# motion_tracker.net
KiCad netlist of a schematic drawn in Altium Designer
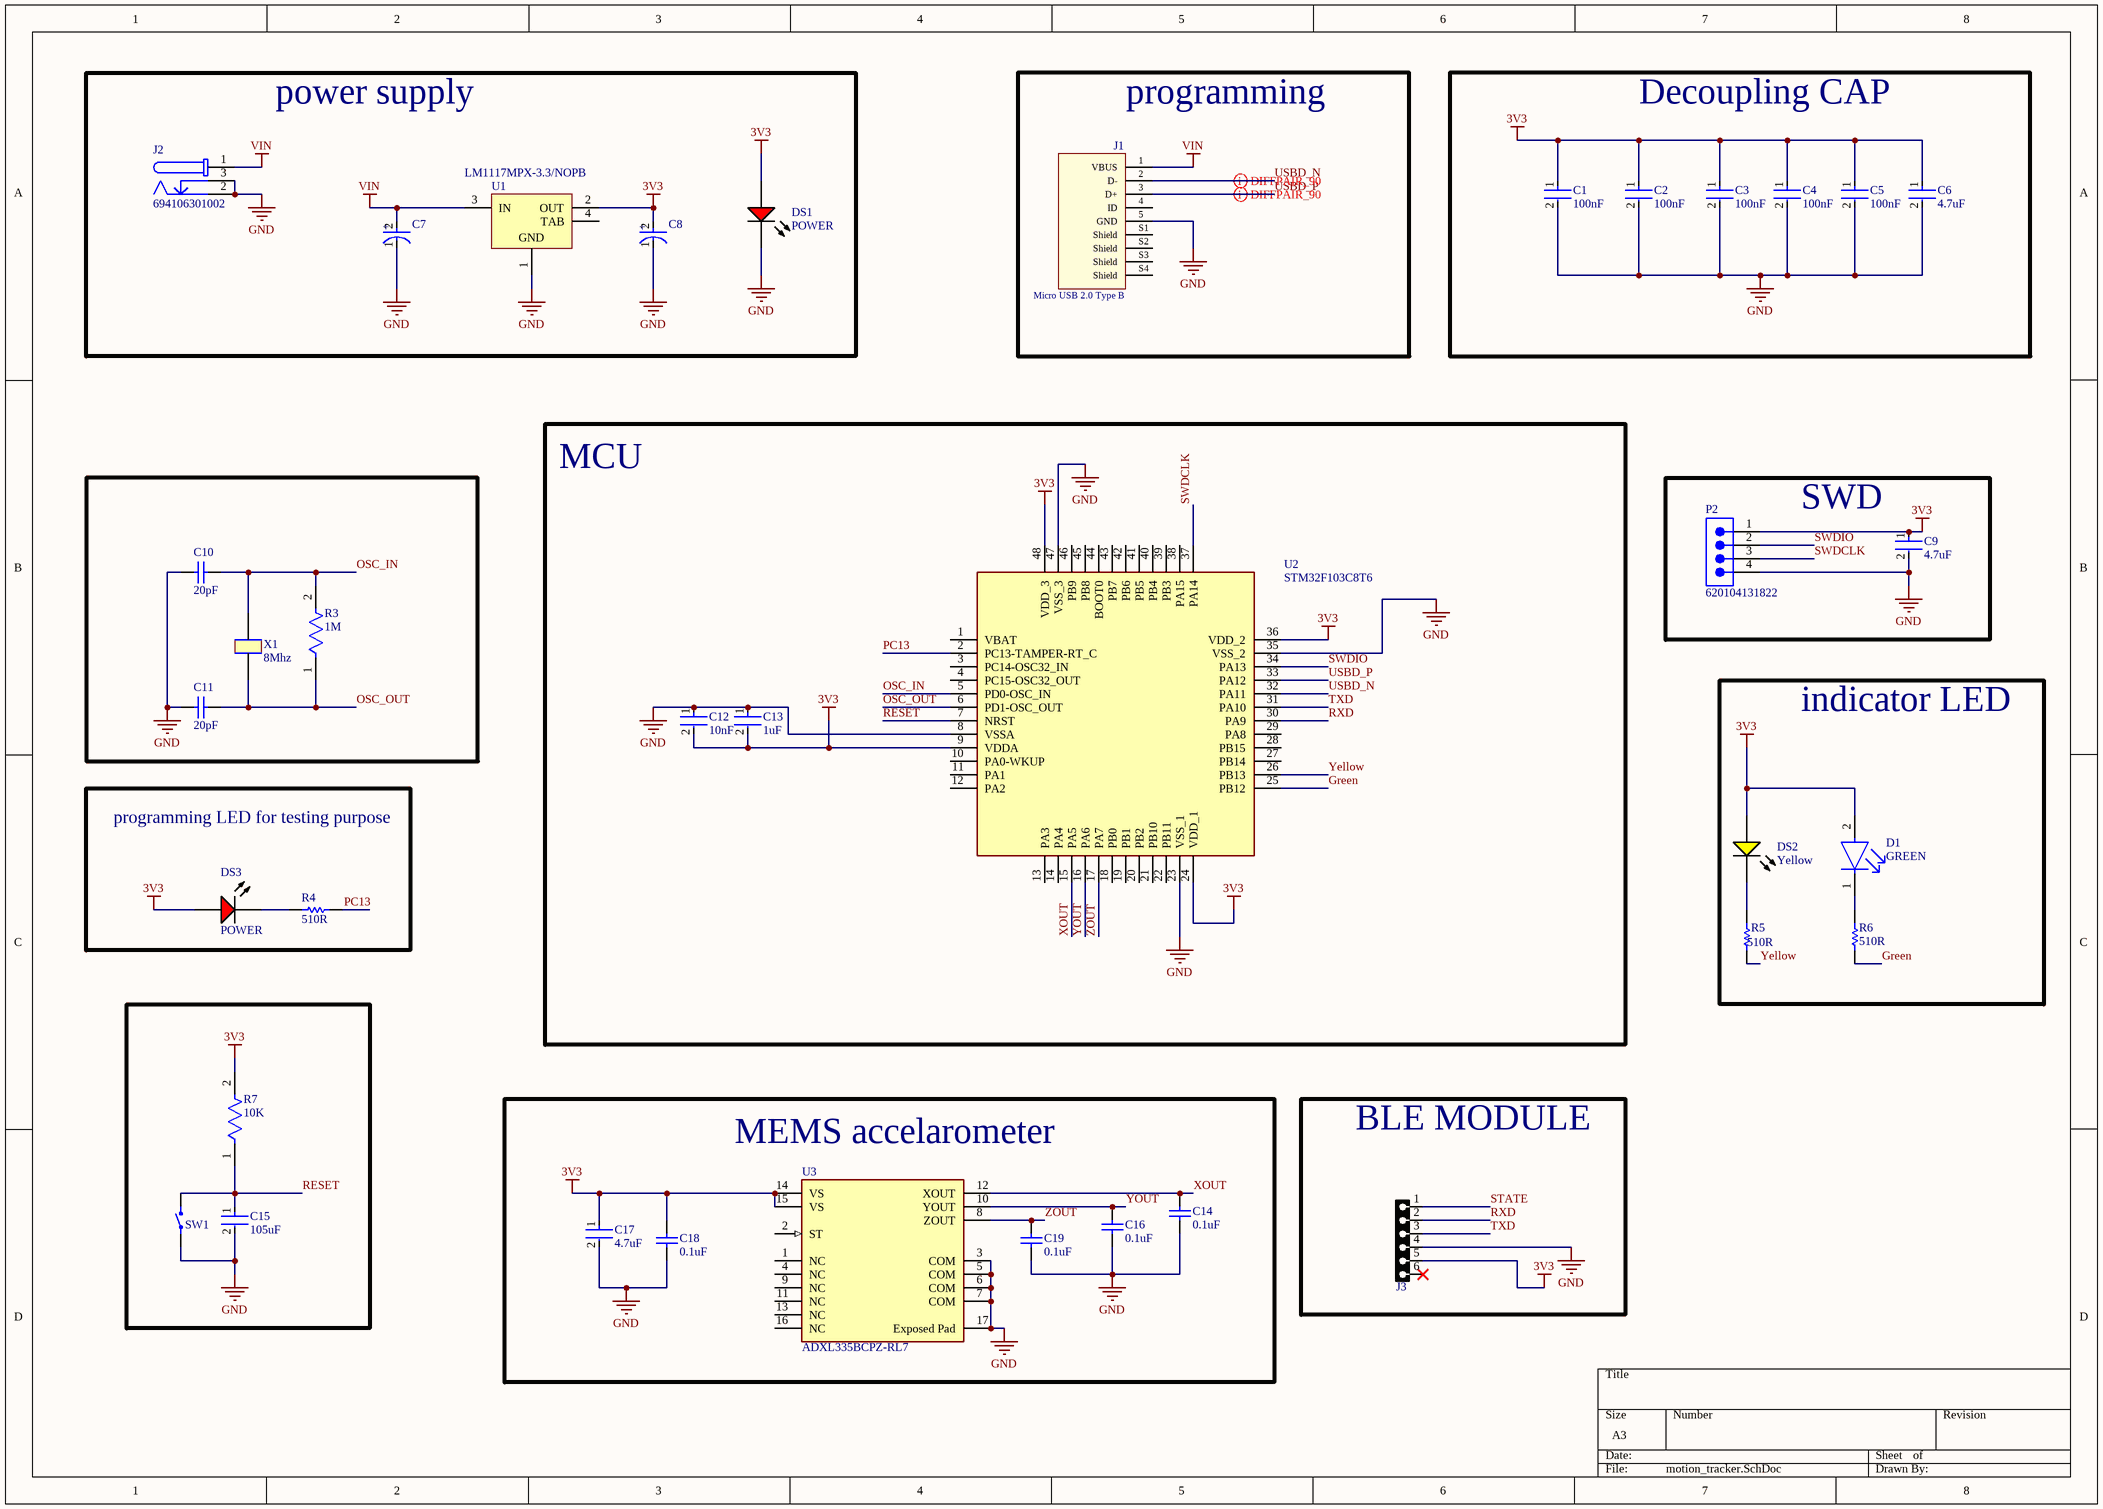
[diagram p0: motion_tracker.SchDoc]

(export (version "E")
  (design (tool "Eeschema 10.0.6"))
  (components
    (comp (ref "C1")
      (value "100nF")
      (footprint "FP-0603-L_1_6_0_15-W_0_81-IPC_C")
      (description "Automotive Ceramic Capacitor, 0603, 100nF, 10%, X7R, 15%, 50V")
      (fields (field (name "VOLTAGE") "50V") (field (name "TOLERANCE") "10%"))
      (libsource (lib "Altium Content Vault") (part "02cd4be3c70576c341d710602a673aa"))
    )
    (comp (ref "C2")
      (value "100nF")
      (footprint "FP-0603-L_1_6_0_15-W_0_81-IPC_C")
      (description "Automotive Ceramic Capacitor, 0603, 100nF, 10%, X7R, 15%, 50V")
      (fields (field (name "VOLTAGE") "50V") (field (name "TOLERANCE") "10%"))
      (libsource (lib "Altium Content Vault") (part "02cd4be3c70576c341d710602a673aa"))
    )
    (comp (ref "C3")
      (value "100nF")
      (footprint "FP-0603-L_1_6_0_15-W_0_81-IPC_C")
      (description "Automotive Ceramic Capacitor, 0603, 100nF, 10%, X7R, 15%, 50V")
      (fields (field (name "VOLTAGE") "50V") (field (name "TOLERANCE") "10%"))
      (libsource (lib "Altium Content Vault") (part "02cd4be3c70576c341d710602a673aa"))
    )
    (comp (ref "C4")
      (value "100nF")
      (footprint "FP-0603-L_1_6_0_15-W_0_81-IPC_C")
      (description "Automotive Ceramic Capacitor, 0603, 100nF, 10%, X7R, 15%, 50V")
      (fields (field (name "VOLTAGE") "50V") (field (name "TOLERANCE") "10%"))
      (libsource (lib "Altium Content Vault") (part "02cd4be3c70576c341d710602a673aa"))
    )
    (comp (ref "C5")
      (value "100nF")
      (footprint "FP-0603-L_1_6_0_15-W_0_81-IPC_C")
      (description "Automotive Ceramic Capacitor, 0603, 100nF, 10%, X7R, 15%, 50V")
      (fields (field (name "VOLTAGE") "50V") (field (name "TOLERANCE") "10%"))
      (libsource (lib "Altium Content Vault") (part "02cd4be3c70576c341d710602a673aa"))
    )
    (comp (ref "C6")
      (value "4.7uF")
      (footprint "FP-0603-L_1_6_0_15-W_0_81-IPC_A")
      (description "General Purpose Ceramic Capacitor, 0603, 4.7uF, 20%, X5R, 15%, 6.3V")
      (fields (field (name "TOLERANCE") "20%") (field (name "VOLTAGE") "6.3V"))
      (libsource (lib "Altium Content Vault") (part "02cd4be3c70576c341d710602a673aa"))
    )
    (comp (ref "C7")
      (value "EEEFP1C100AR")
      (footprint "FP-FPB-MFG")
      (fields (field (name "TOLERANCE") "20%") (field (name "VOLTAGE") "16V"))
      (libsource (lib "Altium Content Vault") (part "203bc49f2ac43e59fd269a8c329ed05"))
    )
    (comp (ref "C8")
      (value "EEEFP1C100AR")
      (footprint "FP-FPB-MFG")
      (fields (field (name "TOLERANCE") "20%") (field (name "VOLTAGE") "16V"))
      (libsource (lib "Altium Content Vault") (part "203bc49f2ac43e59fd269a8c329ed05"))
    )
    (comp (ref "C9")
      (value "4.7uF")
      (footprint "FP-0603-L_1_6_0_15-W_0_81-IPC_A")
      (description "General Purpose Ceramic Capacitor, 0603, 4.7uF, 20%, X5R, 15%, 6.3V")
      (fields (field (name "TOLERANCE") "20%") (field (name "VOLTAGE") "6.3V"))
      (libsource (lib "Altium Content Vault") (part "02cd4be3c70576c341d710602a673aa"))
    )
    (comp (ref "C10")
      (value "20pF")
      (footprint "CAPC1608X90X35NL15T15")
      (fields
        (field (name "PART NUMBER") "06035A200JAT2A")
        (field (name "MANUFACTURER") "AVX Interconnect / Elco")
      )
      (libsource (lib "Altium Content Vault") (part "CAP"))
    )
    (comp (ref "C11")
      (value "20pF")
      (footprint "CAPC1608X90X35NL15T15")
      (fields
        (field (name "PART NUMBER") "06035A200JAT2A")
        (field (name "MANUFACTURER") "AVX Interconnect / Elco")
      )
      (libsource (lib "Altium Content Vault") (part "CAP"))
    )
    (comp (ref "C12")
      (value "10nF")
      (footprint "FP-0603-L_1_6_0_15-W_0_81-IPC_C")
      (description "Automotive Ceramic Capacitor, 0603, 100nF, 10%, X7R, 15%, 50V")
      (fields (field (name "VOLTAGE") "50V") (field (name "TOLERANCE") "10%"))
      (libsource (lib "Altium Content Vault") (part "02cd4be3c70576c341d710602a673aa"))
    )
    (comp (ref "C13")
      (value "1uF")
      (footprint "FP-0603-L_1_6_0_15-W_0_81-IPC_C")
      (description "Automotive Ceramic Capacitor, 0603, 100nF, 10%, X7R, 15%, 50V")
      (fields (field (name "VOLTAGE") "50V") (field (name "TOLERANCE") "10%"))
      (libsource (lib "Altium Content Vault") (part "02cd4be3c70576c341d710602a673aa"))
    )
    (comp (ref "C14")
      (value "0.1uF")
      (footprint "CAPC1608X90X35LL15T15")
      (fields
        (field (name "MANUFACTURER") "AVX Interconnect / Elco")
        (field (name "PART NUMBER") "LD035C104KAB2A")
      )
      (libsource (lib "Altium Content Vault") (part "CAP"))
    )
    (comp (ref "C15")
      (value "105uF")
      (footprint "FP-0603-L_1_6_0_15-W_0_81-IPC_C")
      (description "Automotive Ceramic Capacitor, 0603, 100nF, 10%, X7R, 15%, 50V")
      (fields (field (name "VOLTAGE") "50V") (field (name "TOLERANCE") "10%"))
      (libsource (lib "Altium Content Vault") (part "02cd4be3c70576c341d710602a673aa"))
    )
    (comp (ref "C16")
      (value "0.1uF")
      (footprint "CAPC1608X90X35LL15T15")
      (fields
        (field (name "MANUFACTURER") "AVX Interconnect / Elco")
        (field (name "PART NUMBER") "LD035C104KAB2A")
      )
      (libsource (lib "Altium Content Vault") (part "CAP"))
    )
    (comp (ref "C17")
      (value "4.7uF")
      (footprint "FP-0603-L_1_6_0_15-W_0_81-IPC_A")
      (description "General Purpose Ceramic Capacitor, 0603, 4.7uF, 20%, X5R, 15%, 6.3V")
      (fields (field (name "TOLERANCE") "20%") (field (name "VOLTAGE") "6.3V"))
      (libsource (lib "Altium Content Vault") (part "02cd4be3c70576c341d710602a673aa"))
    )
    (comp (ref "C18")
      (value "0.1uF")
      (footprint "CAPC1608X90X35LL15T15")
      (fields
        (field (name "MANUFACTURER") "AVX Interconnect / Elco")
        (field (name "PART NUMBER") "LD035C104KAB2A")
      )
      (libsource (lib "Altium Content Vault") (part "CAP"))
    )
    (comp (ref "C19")
      (value "0.1uF")
      (footprint "CAPC1608X90X35LL15T15")
      (fields
        (field (name "MANUFACTURER") "AVX Interconnect / Elco")
        (field (name "PART NUMBER") "LD035C104KAB2A")
      )
      (libsource (lib "Altium Content Vault") (part "CAP"))
    )
    (comp (ref "D1")
      (value "GREEN")
      (footprint "FP-LTST-C190GKT-MFG")
      (description "LED GREEN CLEAR CHIP SMD")
      (fields (field (name "VOLTAGE") "2V"))
      (libsource (lib "Altium Content Vault") (part "8706943c75ba83719d021d2fdc84c58"))
    )
    (comp (ref "DS1")
      (value "POWER")
      (footprint "AVAG-HSMX-C190_V")
      (description "LED Uni-Color Red, 52 mW, 20 mA, -40 to 85 degC, 2-Pin SMD, RoHS, Tape and Reel")
      (fields (field (name "MANUFACTURER") "Avago"))
      (libsource (lib "Altium Content Vault") (part "LED-RED-AK-2"))
    )
    (comp (ref "DS2")
      (value "Yellow")
      (footprint "AVAG-HSMX-C190_V")
      (description "LED Uni-Color Yellow, 65 mW, 20 mA, -40 to 85 degC, 2-Pin SMD, RoHS, Tape and Reel")
      (fields (field (name "TOLERANCE") "1%"))
      (libsource (lib "Altium Content Vault") (part "LED-YELLOW-AK-2"))
    )
    (comp (ref "DS3")
      (value "POWER")
      (footprint "AVAG-HSMX-C190_V")
      (description "LED Uni-Color Red, 52 mW, 20 mA, -40 to 85 degC, 2-Pin SMD, RoHS, Tape and Reel")
      (fields (field (name "MANUFACTURER") "Avago"))
      (libsource (lib "Altium Content Vault") (part "LED-RED-AK-2"))
    )
    (comp (ref "J1")
      (value "Micro USB 2.0 Type B")
      (footprint "629105136821")
      (description "Micro USB 2.0 Type B Horizontal SMT 5 Contacts WR-COM")
      (fields (field (name "PARTNUMBER") "629105136821") (field (name "PUBLISHER") "Wurth Elektronik"))
      (libsource (lib "Conn Usb") (part "Micro USB 2.0 Type B Horizonta (SMD) 629105136821"))
    )
    (comp (ref "J2")
      (value "694106301002")
      (footprint "694106301002")
      (libsource (lib "Altium Content Vault") (part "DC Power Jack"))
    )
    (comp (ref "J3")
      (value "HDRF6")
      (footprint "HDRLP_F_1X6")
      (description "CONN, HEADER, Male, pitch: 2.54mm, 6POS")
      (libsource (lib "Conn Header") (part "HDRLP_F_1X6"))
    )
    (comp (ref "P2")
      (value "620104131822")
      (footprint "620104131822")
      (libsource (lib "Altium Content Vault") (part "Header_Male_1R_04P"))
    )
    (comp (ref "R3")
      (value "1M")
      (footprint "FP-ERJ3EK-IPC_C")
      (description "RES SMD 1M OHM 1% 1/10W 0603")
      (fields (field (name "TOLERANCE") "1%"))
      (libsource (lib "Altium Content Vault") (part "1029c3af85768c4190bb7ad29bc67b5"))
    )
    (comp (ref "R4")
      (value "510R")
      (footprint "RESC1608X55X30ML15T15")
      (fields (field (name "MANUFACTURER") "Panasonic") (field (name "PART NUMBER") "ERJ-3GEYJ511V"))
      (libsource (lib "Altium Content Vault") (part "RES"))
    )
    (comp (ref "R5")
      (value "510R")
      (footprint "RESC1608X55X30ML15T15")
      (fields (field (name "MANUFACTURER") "Panasonic") (field (name "PART NUMBER") "ERJ-3GEYJ511V"))
      (libsource (lib "Altium Content Vault") (part "RES"))
    )
    (comp (ref "R6")
      (value "510R")
      (footprint "RESC1608X55X30ML15T15")
      (fields (field (name "MANUFACTURER") "Panasonic") (field (name "PART NUMBER") "ERJ-3GEYJ511V"))
      (libsource (lib "Altium Content Vault") (part "RES"))
    )
    (comp (ref "R7")
      (value "10K")
      (footprint "FP-CRCW0603-HPe3-MFG")
      (description "RES SMD 10K OHM 1% 1/3W 0603")
      (fields (field (name "TOLERANCE") "1%"))
      (libsource (lib "Altium Content Vault") (part "1029c3af85768c4190bb7ad29bc67b5"))
    )
    (comp (ref "SW1")
      (value "Tactile 2PIN 6X3.5mm H4.57mm (SMD)")
      (footprint "SWPBS_SPST_6X3X5")
      (description "Tactile Switch SPST-NO Top Actuated Surface Mount")
      (fields (field (name "PARTNUMBER") "FSMSMTR-ND"))
      (libsource (lib "Switch") (part "Tactile 2PIN 6X3.5mm H4.57mm (SMD)"))
    )
    (comp (ref "U1")
      (value "LM1117MPX-3.3/NOPB")
      (footprint "DCY0004A_L")
      (description "800mA Low-Dropout Linear Regulator, 4-pin SOT-223, Pb-Free")
      (fields (field (name "MANUFACTURER") "Texas Instruments"))
      (libsource (lib "Altium Content Vault") (part "PM-REG-LM1086-SOT4"))
    )
    (comp (ref "U2")
      (value "STM32F103C8T6")
      (footprint "LQFP-48_19.6_393_58X11_SMD")
      (description "ARM® Cortex®-M3 STM32F1 Microcontroller IC 32-Bit 72MHz 64KB (64K x 8) FLASH 48-LQFP (7x7)")
      (fields (field (name "MANUFACTURER") "STMicroelectronics"))
      (libsource (lib "ESTEEMPCBLIB") (part "IC_STM32F103C8T6"))
    )
    (comp (ref "U3")
      (value "ADXL335BCPZ-RL7")
      (footprint "FP-CP-16-14-MFG")
      (description "ACCELEROMETER 3G ANALOG 16LFCSP")
      (libsource (lib "Altium Content Vault") (part "7b2f5658e68b730020a96767d60bf48"))
    )
    (comp (ref "X1")
      (value "8Mhz")
      (footprint "XTAL_314_240X47_SMD")
      (description "8MHz ±30ppm Crystal 32pF 60 Ohms HC-49/US")
      (fields
        (field (name "MANUFACTURER") "Fox Electronics")
        (field (name "MANUFACTURER PART NUMBER") "ECS-80-32-5PX-TR")
      )
      (libsource (lib "ESTEEMPCBLIB") (part "XTAL_8MHZ-ECS-80-32-5PX-SMD"))
    )
  )
  (nets
    (net (code "1") (name "/Green") (class "Default")
      (node (ref "R6") (pin "2") (pinfunction "2_2") (pintype "passive"))
      (node (ref "U2") (pin "25") (pinfunction "PB12_25") (pintype "passive"))
    )
    (net (code "2") (name "/OSC_IN") (class "Default")
      (node (ref "C10") (pin "2") (pinfunction "2_2") (pintype "passive"))
      (node (ref "R3") (pin "2") (pinfunction "2_2") (pintype "passive"))
      (node (ref "U2") (pin "5") (pinfunction "PD0-OSC_IN_5") (pintype "passive"))
      (node (ref "X1") (pin "2") (pinfunction "2_2") (pintype "passive"))
    )
    (net (code "3") (name "/OSC_OUT") (class "Default")
      (node (ref "C11") (pin "2") (pinfunction "2_2") (pintype "passive"))
      (node (ref "R3") (pin "1") (pinfunction "1_1") (pintype "passive"))
      (node (ref "U2") (pin "6") (pinfunction "PD1-OSC_OUT_6") (pintype "passive"))
      (node (ref "X1") (pin "1") (pinfunction "1_1") (pintype "passive"))
    )
    (net (code "4") (name "/PC13") (class "Default")
      (node (ref "R4") (pin "2") (pinfunction "2_2") (pintype "passive"))
      (node (ref "U2") (pin "2") (pinfunction "PC13-TAMPER-RT_C_2") (pintype "passive"))
    )
    (net (code "5") (name "/RESET") (class "Default")
      (node (ref "C15") (pin "1") (pinfunction "1_1") (pintype "passive"))
      (node (ref "R7") (pin "1") (pinfunction "1_1") (pintype "passive"))
      (node (ref "SW1") (pin "2") (pinfunction "2_2") (pintype "passive"))
      (node (ref "U2") (pin "7") (pinfunction "NRST_7") (pintype "passive"))
    )
    (net (code "6") (name "/RXD") (class "Default")
      (node (ref "J3") (pin "2") (pinfunction "2_2") (pintype "passive"))
      (node (ref "U2") (pin "30") (pinfunction "PA9_30") (pintype "passive"))
    )
    (net (code "7") (name "/STATE") (class "Default")
      (node (ref "J3") (pin "1") (pinfunction "1_1") (pintype "passive"))
    )
    (net (code "8") (name "/SWDCLK") (class "Default")
      (node (ref "P2") (pin "3") (pinfunction "3_3") (pintype "passive"))
      (node (ref "U2") (pin "37") (pinfunction "PA14_37") (pintype "passive"))
    )
    (net (code "9") (name "/SWDIO") (class "Default")
      (node (ref "P2") (pin "2") (pinfunction "2_2") (pintype "passive"))
      (node (ref "U2") (pin "34") (pinfunction "PA13_34") (pintype "passive"))
    )
    (net (code "10") (name "/TXD") (class "Default")
      (node (ref "J3") (pin "3") (pinfunction "3_3") (pintype "passive"))
      (node (ref "U2") (pin "31") (pinfunction "PA10_31") (pintype "passive"))
    )
    (net (code "11") (name "/USBD_N") (class "Default")
      (node (ref "J1") (pin "2") (pinfunction "D-_2") (pintype "passive"))
      (node (ref "U2") (pin "32") (pinfunction "PA11_32") (pintype "passive"))
    )
    (net (code "12") (name "/USBD_P") (class "Default")
      (node (ref "J1") (pin "3") (pinfunction "D+_3") (pintype "passive"))
      (node (ref "U2") (pin "33") (pinfunction "PA12_33") (pintype "passive"))
    )
    (net (code "13") (name "/XOUT") (class "Default")
      (node (ref "C14") (pin "2") (pinfunction "2_2") (pintype "passive"))
      (node (ref "U2") (pin "15") (pinfunction "PA5_15") (pintype "passive"))
      (node (ref "U3") (pin "12") (pinfunction "XOUT_12") (pintype "passive"))
    )
    (net (code "14") (name "/YOUT") (class "Default")
      (node (ref "C16") (pin "2") (pinfunction "2_2") (pintype "passive"))
      (node (ref "U2") (pin "16") (pinfunction "PA6_16") (pintype "passive"))
      (node (ref "U3") (pin "10") (pinfunction "YOUT_10") (pintype "passive"))
    )
    (net (code "15") (name "/Yellow") (class "Default")
      (node (ref "R5") (pin "2") (pinfunction "2_2") (pintype "passive"))
      (node (ref "U2") (pin "26") (pinfunction "PB13_26") (pintype "passive"))
    )
    (net (code "16") (name "/ZOUT") (class "Default")
      (node (ref "C19") (pin "2") (pinfunction "2_2") (pintype "passive"))
      (node (ref "U2") (pin "17") (pinfunction "PA7_17") (pintype "passive"))
      (node (ref "U3") (pin "8") (pinfunction "ZOUT_8") (pintype "passive"))
    )
    (net (code "17") (name "3V3") (class "Default")
      (node (ref "C1") (pin "1") (pinfunction "1_1") (pintype "passive"))
      (node (ref "C12") (pin "2") (pinfunction "2_2") (pintype "passive"))
      (node (ref "C13") (pin "2") (pinfunction "2_2") (pintype "passive"))
      (node (ref "C17") (pin "1") (pinfunction "1_1") (pintype "passive"))
      (node (ref "C18") (pin "2") (pinfunction "2_2") (pintype "passive"))
      (node (ref "C2") (pin "1") (pinfunction "1_1") (pintype "passive"))
      (node (ref "C3") (pin "1") (pinfunction "1_1") (pintype "passive"))
      (node (ref "C4") (pin "1") (pinfunction "1_1") (pintype "passive"))
      (node (ref "C5") (pin "1") (pinfunction "1_1") (pintype "passive"))
      (node (ref "C6") (pin "1") (pinfunction "1_1") (pintype "passive"))
      (node (ref "C8") (pin "2") (pinfunction "A_2") (pintype "passive"))
      (node (ref "C9") (pin "1") (pinfunction "1_1") (pintype "passive"))
      (node (ref "D1") (pin "2") (pinfunction "A_2") (pintype "passive"))
      (node (ref "DS1") (pin "1") (pinfunction "A_1") (pintype "passive"))
      (node (ref "DS2") (pin "1") (pinfunction "A_1") (pintype "passive"))
      (node (ref "DS3") (pin "1") (pinfunction "A_1") (pintype "passive"))
      (node (ref "J3") (pin "5") (pinfunction "5_5") (pintype "passive"))
      (node (ref "P2") (pin "1") (pinfunction "1_1") (pintype "passive"))
      (node (ref "R7") (pin "2") (pinfunction "2_2") (pintype "passive"))
      (node (ref "U1") (pin "2") (pinfunction "OUT_2") (pintype "power_in"))
      (node (ref "U2") (pin "24") (pinfunction "VDD_1_24") (pintype "passive"))
      (node (ref "U2") (pin "36") (pinfunction "VDD_2_36") (pintype "passive"))
      (node (ref "U2") (pin "48") (pinfunction "VDD_3_48") (pintype "passive"))
      (node (ref "U2") (pin "9") (pinfunction "VDDA_9") (pintype "passive"))
      (node (ref "U3") (pin "14") (pinfunction "VS_14") (pintype "power_in"))
      (node (ref "U3") (pin "15") (pinfunction "VS_15") (pintype "power_in"))
    )
    (net (code "18") (name "GND") (class "Default")
      (node (ref "C1") (pin "2") (pinfunction "2_2") (pintype "passive"))
      (node (ref "C10") (pin "1") (pinfunction "1_1") (pintype "passive"))
      (node (ref "C11") (pin "1") (pinfunction "1_1") (pintype "passive"))
      (node (ref "C12") (pin "1") (pinfunction "1_1") (pintype "passive"))
      (node (ref "C13") (pin "1") (pinfunction "1_1") (pintype "passive"))
      (node (ref "C14") (pin "1") (pinfunction "1_1") (pintype "passive"))
      (node (ref "C15") (pin "2") (pinfunction "2_2") (pintype "passive"))
      (node (ref "C16") (pin "1") (pinfunction "1_1") (pintype "passive"))
      (node (ref "C17") (pin "2") (pinfunction "2_2") (pintype "passive"))
      (node (ref "C18") (pin "1") (pinfunction "1_1") (pintype "passive"))
      (node (ref "C19") (pin "1") (pinfunction "1_1") (pintype "passive"))
      (node (ref "C2") (pin "2") (pinfunction "2_2") (pintype "passive"))
      (node (ref "C3") (pin "2") (pinfunction "2_2") (pintype "passive"))
      (node (ref "C4") (pin "2") (pinfunction "2_2") (pintype "passive"))
      (node (ref "C5") (pin "2") (pinfunction "2_2") (pintype "passive"))
      (node (ref "C6") (pin "2") (pinfunction "2_2") (pintype "passive"))
      (node (ref "C7") (pin "1") (pinfunction "C_1") (pintype "passive"))
      (node (ref "C8") (pin "1") (pinfunction "C_1") (pintype "passive"))
      (node (ref "C9") (pin "2") (pinfunction "2_2") (pintype "passive"))
      (node (ref "DS1") (pin "2") (pinfunction "K_2") (pintype "passive"))
      (node (ref "J1") (pin "5") (pinfunction "GND_5") (pintype "passive"))
      (node (ref "J2") (pin "2") (pinfunction "2_2") (pintype "passive"))
      (node (ref "J2") (pin "3") (pinfunction "3_3") (pintype "passive"))
      (node (ref "J3") (pin "4") (pinfunction "4_4") (pintype "passive"))
      (node (ref "P2") (pin "4") (pinfunction "4_4") (pintype "passive"))
      (node (ref "SW1") (pin "1") (pinfunction "1_1") (pintype "passive"))
      (node (ref "U1") (pin "1") (pinfunction "GND_1") (pintype "power_in"))
      (node (ref "U2") (pin "23") (pinfunction "VSS_1_23") (pintype "passive"))
      (node (ref "U2") (pin "35") (pinfunction "VSS_2_35") (pintype "passive"))
      (node (ref "U2") (pin "47") (pinfunction "VSS_3_47") (pintype "passive"))
      (node (ref "U2") (pin "8") (pinfunction "VSSA_8") (pintype "passive"))
      (node (ref "U3") (pin "17") (pinfunction "Exposed_Pad_17") (pintype "passive"))
      (node (ref "U3") (pin "3") (pinfunction "COM_3") (pintype "power_in"))
      (node (ref "U3") (pin "5") (pinfunction "COM_5") (pintype "power_in"))
      (node (ref "U3") (pin "6") (pinfunction "COM_6") (pintype "power_in"))
      (node (ref "U3") (pin "7") (pinfunction "COM_7") (pintype "power_in"))
    )
    (net (code "19") (name "Net-(D1-C)") (class "Default")
      (node (ref "D1") (pin "1") (pinfunction "C_1") (pintype "passive"))
      (node (ref "R6") (pin "1") (pinfunction "1_1") (pintype "passive"))
    )
    (net (code "20") (name "Net-(DS2-K)") (class "Default")
      (node (ref "DS2") (pin "2") (pinfunction "K_2") (pintype "passive"))
      (node (ref "R5") (pin "1") (pinfunction "1_1") (pintype "passive"))
    )
    (net (code "21") (name "Net-(DS3-K)") (class "Default")
      (node (ref "DS3") (pin "2") (pinfunction "K_2") (pintype "passive"))
      (node (ref "R4") (pin "1") (pinfunction "1_1") (pintype "passive"))
    )
    (net (code "22") (name "VIN") (class "Default")
      (node (ref "C7") (pin "2") (pinfunction "A_2") (pintype "passive"))
      (node (ref "J1") (pin "1") (pinfunction "VBUS_1") (pintype "passive"))
      (node (ref "J2") (pin "1") (pinfunction "1_1") (pintype "passive"))
      (node (ref "U1") (pin "3") (pinfunction "IN_3") (pintype "power_in"))
    )
    (net (code "23") (name "unconnected-(J1-ID-Pad4)") (class "Default")
      (node (ref "J1") (pin "4") (pinfunction "ID_4") (pintype "passive"))
    )
    (net (code "24") (name "unconnected-(J1-Shield-PadS1)") (class "Default")
      (node (ref "J1") (pin "S1") (pinfunction "Shield_S1") (pintype "passive"))
    )
    (net (code "25") (name "unconnected-(J1-Shield-PadS2)") (class "Default")
      (node (ref "J1") (pin "S2") (pinfunction "Shield_S2") (pintype "passive"))
    )
    (net (code "26") (name "unconnected-(J1-Shield-PadS3)") (class "Default")
      (node (ref "J1") (pin "S3") (pinfunction "Shield_S3") (pintype "passive"))
    )
    (net (code "27") (name "unconnected-(J1-Shield-PadS4)") (class "Default")
      (node (ref "J1") (pin "S4") (pinfunction "Shield_S4") (pintype "passive"))
    )
    (net (code "28") (name "unconnected-(J3-Pad6)") (class "Default")
      (node (ref "J3") (pin "6") (pinfunction "6_6") (pintype "passive+no_connect"))
    )
    (net (code "29") (name "unconnected-(U1-TAB-Pad4)") (class "Default")
      (node (ref "U1") (pin "4") (pinfunction "TAB_4") (pintype "power_in"))
    )
    (net (code "30") (name "unconnected-(U2-BOOT0-Pad44)") (class "Default")
      (node (ref "U2") (pin "44") (pinfunction "BOOT0_44") (pintype "passive"))
    )
    (net (code "31") (name "unconnected-(U2-PA0-WKUP-Pad10)") (class "Default")
      (node (ref "U2") (pin "10") (pinfunction "PA0-WKUP_10") (pintype "passive"))
    )
    (net (code "32") (name "unconnected-(U2-PA1-Pad11)") (class "Default")
      (node (ref "U2") (pin "11") (pinfunction "PA1_11") (pintype "passive"))
    )
    (net (code "33") (name "unconnected-(U2-PA2-Pad12)") (class "Default")
      (node (ref "U2") (pin "12") (pinfunction "PA2_12") (pintype "passive"))
    )
    (net (code "34") (name "unconnected-(U2-PA3-Pad13)") (class "Default")
      (node (ref "U2") (pin "13") (pinfunction "PA3_13") (pintype "passive"))
    )
    (net (code "35") (name "unconnected-(U2-PA4-Pad14)") (class "Default")
      (node (ref "U2") (pin "14") (pinfunction "PA4_14") (pintype "passive"))
    )
    (net (code "36") (name "unconnected-(U2-PA8-Pad29)") (class "Default")
      (node (ref "U2") (pin "29") (pinfunction "PA8_29") (pintype "passive"))
    )
    (net (code "37") (name "unconnected-(U2-PA15-Pad38)") (class "Default")
      (node (ref "U2") (pin "38") (pinfunction "PA15_38") (pintype "passive"))
    )
    (net (code "38") (name "unconnected-(U2-PB0-Pad18)") (class "Default")
      (node (ref "U2") (pin "18") (pinfunction "PB0_18") (pintype "passive"))
    )
    (net (code "39") (name "unconnected-(U2-PB1-Pad19)") (class "Default")
      (node (ref "U2") (pin "19") (pinfunction "PB1_19") (pintype "passive"))
    )
    (net (code "40") (name "unconnected-(U2-PB2-Pad20)") (class "Default")
      (node (ref "U2") (pin "20") (pinfunction "PB2_20") (pintype "passive"))
    )
    (net (code "41") (name "unconnected-(U2-PB3-Pad39)") (class "Default")
      (node (ref "U2") (pin "39") (pinfunction "PB3_39") (pintype "passive"))
    )
    (net (code "42") (name "unconnected-(U2-PB4-Pad40)") (class "Default")
      (node (ref "U2") (pin "40") (pinfunction "PB4_40") (pintype "passive"))
    )
    (net (code "43") (name "unconnected-(U2-PB5-Pad41)") (class "Default")
      (node (ref "U2") (pin "41") (pinfunction "PB5_41") (pintype "passive"))
    )
    (net (code "44") (name "unconnected-(U2-PB6-Pad42)") (class "Default")
      (node (ref "U2") (pin "42") (pinfunction "PB6_42") (pintype "passive"))
    )
    (net (code "45") (name "unconnected-(U2-PB7-Pad43)") (class "Default")
      (node (ref "U2") (pin "43") (pinfunction "PB7_43") (pintype "passive"))
    )
    (net (code "46") (name "unconnected-(U2-PB8-Pad45)") (class "Default")
      (node (ref "U2") (pin "45") (pinfunction "PB8_45") (pintype "passive"))
    )
    (net (code "47") (name "unconnected-(U2-PB9-Pad46)") (class "Default")
      (node (ref "U2") (pin "46") (pinfunction "PB9_46") (pintype "passive"))
    )
    (net (code "48") (name "unconnected-(U2-PB10-Pad21)") (class "Default")
      (node (ref "U2") (pin "21") (pinfunction "PB10_21") (pintype "passive"))
    )
    (net (code "49") (name "unconnected-(U2-PB11-Pad22)") (class "Default")
      (node (ref "U2") (pin "22") (pinfunction "PB11_22") (pintype "passive"))
    )
    (net (code "50") (name "unconnected-(U2-PB14-Pad27)") (class "Default")
      (node (ref "U2") (pin "27") (pinfunction "PB14_27") (pintype "passive"))
    )
    (net (code "51") (name "unconnected-(U2-PB15-Pad28)") (class "Default")
      (node (ref "U2") (pin "28") (pinfunction "PB15_28") (pintype "passive"))
    )
    (net (code "52") (name "unconnected-(U2-PC14-OSC32_IN-Pad3)") (class "Default")
      (node (ref "U2") (pin "3") (pinfunction "PC14-OSC32_IN_3") (pintype "passive"))
    )
    (net (code "53") (name "unconnected-(U2-PC15-OSC32_OUT-Pad4)") (class "Default")
      (node (ref "U2") (pin "4") (pinfunction "PC15-OSC32_OUT_4") (pintype "passive"))
    )
    (net (code "54") (name "unconnected-(U2-VBAT-Pad1)") (class "Default")
      (node (ref "U2") (pin "1") (pinfunction "VBAT_1") (pintype "passive"))
    )
    (net (code "55") (name "unconnected-(U3-NC-Pad1)") (class "Default")
      (node (ref "U3") (pin "1") (pinfunction "NC_1") (pintype "passive"))
    )
    (net (code "56") (name "unconnected-(U3-NC-Pad4)") (class "Default")
      (node (ref "U3") (pin "4") (pinfunction "NC_4") (pintype "passive"))
    )
    (net (code "57") (name "unconnected-(U3-NC-Pad9)") (class "Default")
      (node (ref "U3") (pin "9") (pinfunction "NC_9") (pintype "passive"))
    )
    (net (code "58") (name "unconnected-(U3-NC-Pad11)") (class "Default")
      (node (ref "U3") (pin "11") (pinfunction "NC_11") (pintype "passive"))
    )
    (net (code "59") (name "unconnected-(U3-NC-Pad13)") (class "Default")
      (node (ref "U3") (pin "13") (pinfunction "NC_13") (pintype "passive"))
    )
    (net (code "60") (name "unconnected-(U3-NC-Pad16)") (class "Default")
      (node (ref "U3") (pin "16") (pinfunction "NC_16") (pintype "passive"))
    )
    (net (code "61") (name "unconnected-(U3-ST-Pad2)") (class "Default")
      (node (ref "U3") (pin "2") (pinfunction "ST_2") (pintype "input"))
    )
  )
)
